# FMC_ADC_100M_10B_16CHA_TDC.net
KiCad netlist of a schematic drawn in Altium Designer
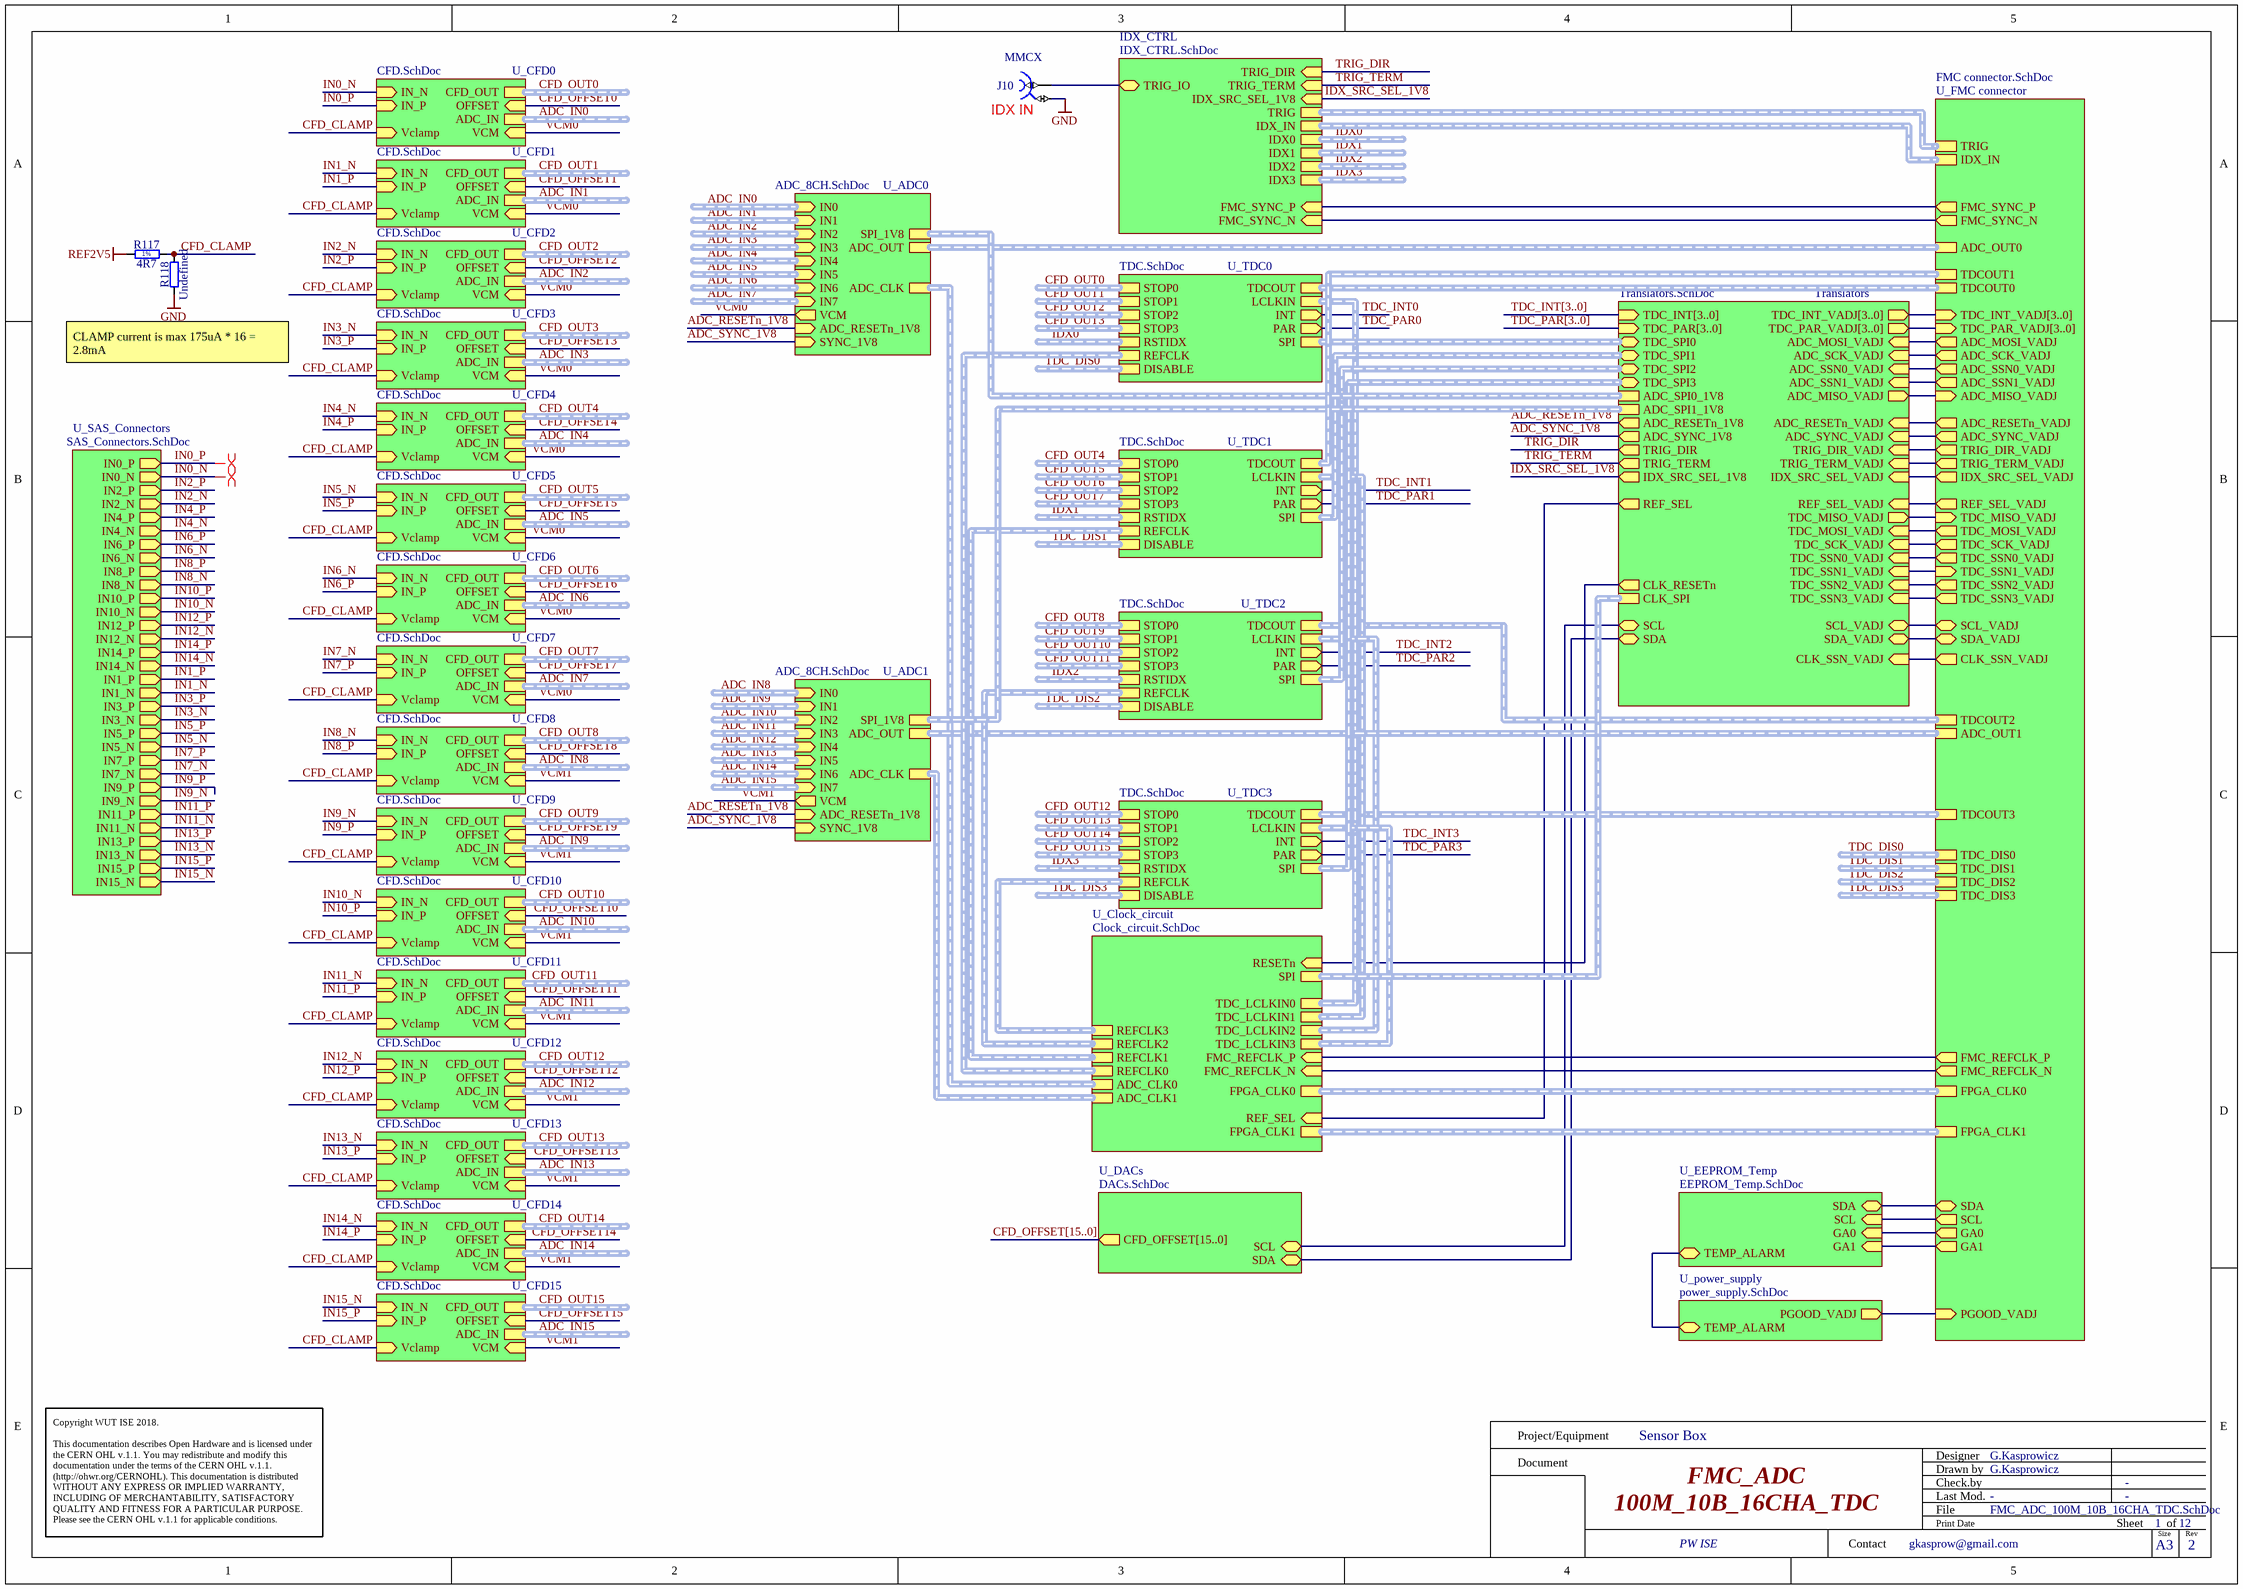
[diagram p0: FMC_ADC_100M_10B_16CHA_TDC.SchDoc]

(export (version "E")
  (design (tool "Eeschema 10.0.6"))
  (components
    (comp (ref "J10")
      (value "Coax_1Female_1Shield")
      (footprint "HUBER-SUHNER_85_MMCX-50-0-1/111 OH")
      (fields
        (field (name "PART NUMBER") "HUBER-SUHNER_85_MMCX-50-0-1/111 OH")
        (field (name "FAMILY") "MMCX")
        (field (name "MANUFACTURER") "HUBER+SUHNER")
        (field (name "MANUFACTURER PART NUMBER") "85_MMCX-50-0-1/111 OH")
        (field (name "AUTHOR") "CERN DEM JLC")
      )
      (libsource (lib "Connectors") (part "Coax_1Female_1Shield"))
    )
    (comp (ref "R117")
      (value "4R7")
      (footprint "RESC1005X40N")
      (description "Resistor - 1%")
      (fields
        (field (name "PART NUMBER") "R0402_4R7_1%_0.0625W_200PPM")
        (field (name "POWER") "0.0625W")
        (field (name "AUTHOR") "CERN DEM JLC")
      )
      (libsource (lib "Resistors") (part "Resistor - 1%"))
    )
    (comp (ref "R118")
      (value "Undefined")
      (footprint "RESC1005X40N")
      (description "Resistor")
      (fields (field (name "PART NUMBER") "R0402_NO-VALUE") (field (name "AUTHOR") "CERN DEM JLC"))
      (libsource (lib "Resistors") (part "Resistor"))
    )
  )
  (nets
    (net (code "56") (name "/CFD_CLAMP") (class "Default")
      (node (ref "R117") (pin "2") (pinfunction "2_2") (pintype "passive"))
      (node (ref "R118") (pin "2") (pinfunction "2_2") (pintype "passive"))
    )
    (net (code "167") (name "/TRIG_IO") (class "Default")
      (node (ref "J10") (pin "1") (pinfunction "1_1") (pintype "bidirectional"))
    )
    (net (code "213") (name "GND") (class "Default")
      (node (ref "J10") (pin "2") (pinfunction "2_2") (pintype "bidirectional"))
      (node (ref "R118") (pin "1") (pinfunction "1_1") (pintype "passive"))
    )
    (net (code "214") (name "REF2V5") (class "Default")
      (node (ref "R117") (pin "1") (pinfunction "1_1") (pintype "passive"))
    )
  )
)
